# 13-Power-P3V3.net
KiCad netlist of a schematic drawn in Altium Designer
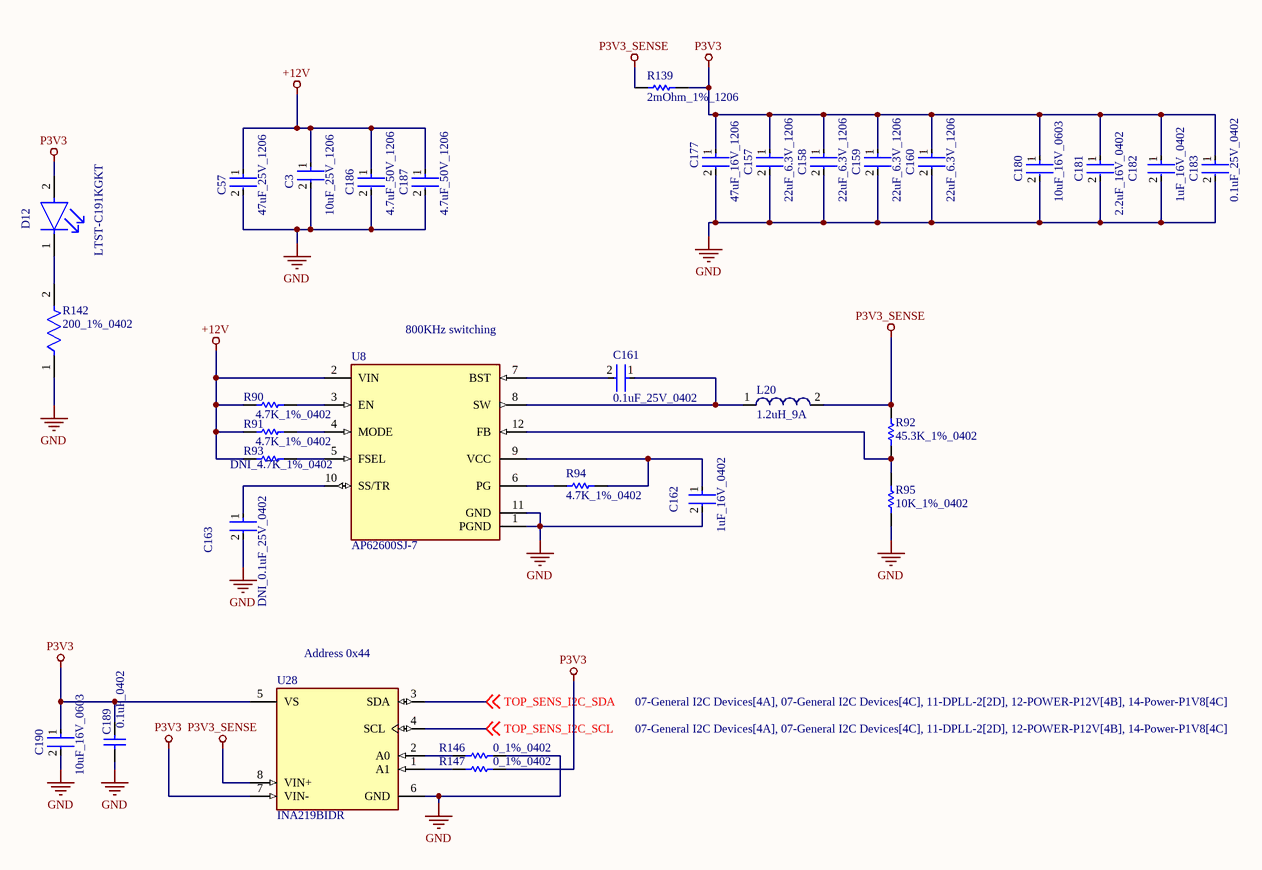
[diagram p0: 13-Power-P3V3.SchDoc]

(export (version "E")
  (design (tool "Eeschema 10.0.6"))
  (components
    (comp (ref "C3")
      (value "10uF_25V_1206")
      (footprint "FP-1206-L_3_2_0_2-W_1_6_0-IPC_A")
      (description "General Purpose Ceramic Capacitor, 1206, 10uF, 20%, X5R, 15%, 25V")
      (fields (field (name "TOLERANCE") "20%"))
      (libsource (lib "Altium Content Vault") (part "02cd4be3c70576c341d710602a673aa"))
    )
    (comp (ref "C57")
      (value "47uF_25V_1206")
      (footprint "FP-C3216-160-0_2-MFG")
      (description "Multilayer Ceramic Capacitors 47uF ±20% 25V X5R SMD 1206")
      (fields (field (name "VOLTAGE") "25V") (field (name "TOLERANCE") "20%"))
      (libsource (lib "Altium Content Vault") (part "11868f565c42a9108669ba33697ecf6"))
    )
    (comp (ref "C157")
      (value "22uF_6.3V_1206")
      (footprint "FP-1206-L_3_2_0_2-W_1_6_0-IPC_C")
      (description "General Purpose Ceramic Capacitor, 1206, 22uF, 20%, X5R, 15%, 6.3V")
      (fields (field (name "TOLERANCE") "20%") (field (name "VOLTAGE") "6.3V"))
      (libsource (lib "Altium Content Vault") (part "02cd4be3c70576c341d710602a673aa"))
    )
    (comp (ref "C158")
      (value "22uF_6.3V_1206")
      (footprint "FP-1206-L_3_2_0_2-W_1_6_0-IPC_C")
      (description "General Purpose Ceramic Capacitor, 1206, 22uF, 20%, X5R, 15%, 6.3V")
      (fields (field (name "TOLERANCE") "20%") (field (name "VOLTAGE") "6.3V"))
      (libsource (lib "Altium Content Vault") (part "02cd4be3c70576c341d710602a673aa"))
    )
    (comp (ref "C159")
      (value "22uF_6.3V_1206")
      (footprint "FP-1206-L_3_2_0_2-W_1_6_0-IPC_C")
      (description "General Purpose Ceramic Capacitor, 1206, 22uF, 20%, X5R, 15%, 6.3V")
      (fields (field (name "TOLERANCE") "20%") (field (name "VOLTAGE") "6.3V"))
      (libsource (lib "Altium Content Vault") (part "02cd4be3c70576c341d710602a673aa"))
    )
    (comp (ref "C160")
      (value "22uF_6.3V_1206")
      (footprint "FP-1206-L_3_2_0_2-W_1_6_0-IPC_C")
      (description "General Purpose Ceramic Capacitor, 1206, 22uF, 20%, X5R, 15%, 6.3V")
      (fields (field (name "TOLERANCE") "20%") (field (name "VOLTAGE") "6.3V"))
      (libsource (lib "Altium Content Vault") (part "02cd4be3c70576c341d710602a673aa"))
    )
    (comp (ref "C161")
      (value "0.1uF_25V_0402")
      (footprint "FP-0402-L_1_0_1-W_0_5_0_1-IPC_C")
      (description "General Purpose Ceramic Capacitor, 0402, 100nF, 10%, X7R, 15%, 25V")
      (fields (field (name "VOLTAGE") "25V") (field (name "TOLERANCE") "10%"))
      (libsource (lib "Altium Content Vault") (part "b4654b650e69147ec39a6b967a45e02"))
    )
    (comp (ref "C162")
      (value "1uF_16V_0402")
      (footprint "FP-0402-L_1_0_0_05-W_0_5-IPC_A")
      (description "None")
      (fields (field (name "TOLERANCE") "10%"))
      (libsource (lib "Altium Content Vault") (part "b4654b650e69147ec39a6b967a45e02"))
    )
    (comp (ref "C163")
      (value "DNI_0.1uF_25V_0402")
      (footprint "FP-0402-L_1_0_1-W_0_5_0_1-IPC_C")
      (description "General Purpose Ceramic Capacitor, 0402, 100nF, 10%, X7R, 15%, 25V")
      (fields (field (name "VOLTAGE") "25V") (field (name "TOLERANCE") "10%"))
      (libsource (lib "Altium Content Vault") (part "b4654b650e69147ec39a6b967a45e02"))
    )
    (comp (ref "C177")
      (value "47uF_16V_1206")
      (footprint "FP-C3216-160-0_2-MFG")
      (description "Multilayer Ceramic Capacitors 47uF ±20% 16V X5R SMD 1206")
      (fields (field (name "TOLERANCE") "20%"))
      (libsource (lib "Altium Content Vault") (part "11868f565c42a9108669ba33697ecf6"))
    )
    (comp (ref "C180")
      (value "10uF_16V_0603")
      (footprint "FP-0603-L_1_6_0_2-W_0_8_0-MFG")
      (description "Multilayer Ceramic Capacitor 10uF 16V X5R 20% SMD 0603 T/R")
      (fields (field (name "TOLERANCE") "20%"))
      (libsource (lib "Altium Content Vault") (part "b4654b650e69147ec39a6b967a45e02"))
    )
    (comp (ref "C181")
      (value "2.2uF_16V_0402")
      (footprint "FP-C1005-050-0_05-IPC_A")
      (description "Multilayer Ceramic Capacitors 2.2μF ±10% 16V X5R SMD 0402")
      (fields (field (name "TOLERANCE") "10%"))
      (libsource (lib "Altium Content Vault") (part "b4654b650e69147ec39a6b967a45e02"))
    )
    (comp (ref "C182")
      (value "1uF_16V_0402")
      (footprint "FP-0402-L_1_0_0_05-W_0_5-IPC_A")
      (description "None")
      (fields (field (name "TOLERANCE") "10%"))
      (libsource (lib "Altium Content Vault") (part "b4654b650e69147ec39a6b967a45e02"))
    )
    (comp (ref "C183")
      (value "0.1uF_25V_0402")
      (footprint "FP-0402-L_1_0_1-W_0_5_0_1-IPC_C")
      (description "General Purpose Ceramic Capacitor, 0402, 100nF, 10%, X7R, 15%, 25V")
      (fields (field (name "VOLTAGE") "25V") (field (name "TOLERANCE") "10%"))
      (libsource (lib "Altium Content Vault") (part "b4654b650e69147ec39a6b967a45e02"))
    )
    (comp (ref "C186")
      (value "4.7uF_50V_1206")
      (footprint "FP-GRM31C-0_2-e0_3_0_8-IPC_C")
      (description "Chip Multilayer Ceramic Capacitors for General Purpose, 1206, 4.7uF, X7R, 15%, 10%, 50V")
      (fields (field (name "VOLTAGE") "50V") (field (name "TOLERANCE") "10%"))
      (libsource (lib "Altium Content Vault") (part "02cd4be3c70576c341d710602a673aa"))
    )
    (comp (ref "C187")
      (value "4.7uF_50V_1206")
      (footprint "FP-GRM31C-0_2-e0_3_0_8-IPC_C")
      (description "Chip Multilayer Ceramic Capacitors for General Purpose, 1206, 4.7uF, X7R, 15%, 10%, 50V")
      (fields (field (name "VOLTAGE") "50V") (field (name "TOLERANCE") "10%"))
      (libsource (lib "Altium Content Vault") (part "02cd4be3c70576c341d710602a673aa"))
    )
    (comp (ref "C189")
      (value "0.1uF_0402")
      (footprint "CAPC1005X56X25NL10T15")
      (fields
        (field (name "PART NUMBER") "LD02YD104KAB2A")
        (field (name "MANUFACTURER") "AVX Interconnect / Elco")
      )
      (libsource (lib "Altium Content Vault") (part "CAP"))
    )
    (comp (ref "C190")
      (value "10uF_16V_0603")
      (footprint "FP-0603-L_1_6_0_2-W_0_8_0-MFG")
      (description "Multilayer Ceramic Capacitor 10uF 16V X5R 20% SMD 0603 T/R")
      (fields (field (name "TOLERANCE") "20%"))
      (libsource (lib "Altium Content Vault") (part "b4654b650e69147ec39a6b967a45e02"))
    )
    (comp (ref "D12")
      (value "LTST-C191KGKT")
      (footprint "FP-LTST-C191KGKT-MFG")
      (description "LED GREEN CLEAR SMD")
      (libsource (lib "Altium Content Vault") (part "8706943c75ba83719d021d2fdc84c58"))
    )
    (comp (ref "L20")
      (value "1.2uH_9A")
      (footprint "WE-LHMI 7050")
      (description "SMD Power Inductor WE-LHMI, L=1.2 µH")
      (fields (field (name "MANUFACTURER") "Wuerth Elektronik") (field (name "PARTNUMBER") "74437349012"))
      (libsource (lib "Altium Content Vault") (part "WE-IND-INDUCTOR-2"))
    )
    (comp (ref "R90")
      (value "4.7K_1%_0402")
      (footprint "RESC1005X40X25NL10T10")
      (fields (field (name "MANUFACTURER") "Bourns") (field (name "PART NUMBER") "CR0402-FX-4701GLF"))
      (libsource (lib "Altium Content Vault") (part "RES"))
    )
    (comp (ref "R91")
      (value "4.7K_1%_0402")
      (footprint "RESC1005X40X25NL10T10")
      (fields (field (name "MANUFACTURER") "Bourns") (field (name "PART NUMBER") "CR0402-FX-4701GLF"))
      (libsource (lib "Altium Content Vault") (part "RES"))
    )
    (comp (ref "R92")
      (value "45.3K_1%_0402")
      (footprint "RESC1005X40X25ML05T10")
      (fields (field (name "PART NUMBER") "RC0402FR-0745K3L") (field (name "MANUFACTURER") "Yageo / Phycomp"))
      (libsource (lib "Altium Content Vault") (part "RES"))
    )
    (comp (ref "R93")
      (value "DNI_4.7K_1%_0402")
      (footprint "RESC1005X40X25NL10T10")
      (fields (field (name "MANUFACTURER") "Bourns") (field (name "PART NUMBER") "CR0402-FX-4701GLF"))
      (libsource (lib "Altium Content Vault") (part "RES"))
    )
    (comp (ref "R94")
      (value "4.7K_1%_0402")
      (footprint "RESC1005X40X25NL10T10")
      (fields (field (name "MANUFACTURER") "Bourns") (field (name "PART NUMBER") "CR0402-FX-4701GLF"))
      (libsource (lib "Altium Content Vault") (part "RES"))
    )
    (comp (ref "R95")
      (value "10K_1%_0402")
      (footprint "RESC1005X40X25NL10T10")
      (fields (field (name "MANUFACTURER") "Bourns") (field (name "PART NUMBER") "CR0402-FX-1002GLF"))
      (libsource (lib "Altium Content Vault") (part "RES"))
    )
    (comp (ref "R139")
      (value "2mOhm_1%_1206")
      (footprint "RESC3216X89X64NL25T25")
      (fields (field (name "MANUFACTURER") "Vishay Dale") (field (name "PART NUMBER") "WSL12062L000FEA18"))
      (libsource (lib "Altium Content Vault") (part "RES"))
    )
    (comp (ref "R142")
      (value "200_1%_0402")
      (footprint "FP-ERJ2RK-IPC_A")
      (description "RES SMD 200 OHM 1% 1/10W 0402")
      (fields (field (name "TOLERANCE") "1%"))
      (libsource (lib "Altium Content Vault") (part "1029c3af85768c4190bb7ad29bc67b5"))
    )
    (comp (ref "R146")
      (value "0_1%_0402")
      (footprint "RESC1005X40X25LL05T05")
      (description "Chip Resistor, 0 Ohm, 0.1 W, -55 to 155 degC, 0402 (1005 Metric), RoHS, Tape and Reel")
      (fields (field (name "MANUFACTURER") "Panasonic") (field (name "TOLERANCE") "5%"))
      (libsource (lib "Altium Content Vault") (part "RES-2"))
    )
    (comp (ref "R147")
      (value "0_1%_0402")
      (footprint "RESC1005X40X25LL05T05")
      (description "Chip Resistor, 0 Ohm, 0.1 W, -55 to 155 degC, 0402 (1005 Metric), RoHS, Tape and Reel")
      (fields (field (name "MANUFACTURER") "Panasonic") (field (name "TOLERANCE") "5%"))
      (libsource (lib "Altium Content Vault") (part "RES-2"))
    )
    (comp (ref "U8")
      (value "AP62600SJ-7")
      (footprint "FP-V-QFN2030-12_Type_A-MFG")
      (description "DCDC CONV HV BUCK,V-QFN2030-12")
      (libsource (lib "Altium Content Vault") (part "03c86ce2703f4b33b3045e94f7be521"))
    )
    (comp (ref "U28")
      (value "INA219BIDR")
      (footprint "FP-D0008A-MFG")
      (description "IC MONITOR PWR/CURR BIDIR 8-SOIC")
      (libsource (lib "Altium Content Vault") (part "41cc1aee4cbc9fa2660a15773fa0e79"))
    )
  )
  (nets
    (net (code "1") (name "+12V") (class "Default")
      (node (ref "C186") (pin "1") (pinfunction "1_1") (pintype "passive"))
      (node (ref "C187") (pin "1") (pinfunction "1_1") (pintype "passive"))
      (node (ref "C3") (pin "1") (pinfunction "1_1") (pintype "passive"))
      (node (ref "C57") (pin "1") (pinfunction "1_1") (pintype "passive"))
      (node (ref "R90") (pin "1") (pinfunction "1_1") (pintype "passive"))
      (node (ref "R91") (pin "1") (pinfunction "1_1") (pintype "passive"))
      (node (ref "R93") (pin "1") (pinfunction "1_1") (pintype "passive"))
      (node (ref "U8") (pin "2") (pinfunction "VIN_2") (pintype "power_in"))
    )
    (net (code "2") (name "GND") (class "Default")
      (node (ref "C157") (pin "2") (pinfunction "2_2") (pintype "passive"))
      (node (ref "C158") (pin "2") (pinfunction "2_2") (pintype "passive"))
      (node (ref "C159") (pin "2") (pinfunction "2_2") (pintype "passive"))
      (node (ref "C160") (pin "2") (pinfunction "2_2") (pintype "passive"))
      (node (ref "C162") (pin "2") (pinfunction "2_2") (pintype "passive"))
      (node (ref "C163") (pin "2") (pinfunction "2_2") (pintype "passive"))
      (node (ref "C177") (pin "2") (pinfunction "2_2") (pintype "passive"))
      (node (ref "C180") (pin "2") (pinfunction "2_2") (pintype "passive"))
      (node (ref "C181") (pin "2") (pinfunction "2_2") (pintype "passive"))
      (node (ref "C182") (pin "2") (pinfunction "2_2") (pintype "passive"))
      (node (ref "C183") (pin "2") (pinfunction "2_2") (pintype "passive"))
      (node (ref "C186") (pin "2") (pinfunction "2_2") (pintype "passive"))
      (node (ref "C187") (pin "2") (pinfunction "2_2") (pintype "passive"))
      (node (ref "C189") (pin "1") (pinfunction "1_1") (pintype "passive"))
      (node (ref "C190") (pin "2") (pinfunction "2_2") (pintype "passive"))
      (node (ref "C3") (pin "2") (pinfunction "2_2") (pintype "passive"))
      (node (ref "C57") (pin "2") (pinfunction "2_2") (pintype "passive"))
      (node (ref "R142") (pin "1") (pinfunction "1_1") (pintype "passive"))
      (node (ref "R146") (pin "2") (pinfunction "2_2") (pintype "passive"))
      (node (ref "R95") (pin "1") (pinfunction "1_1") (pintype "passive"))
      (node (ref "U28") (pin "6") (pinfunction "GND_6") (pintype "power_in"))
      (node (ref "U8") (pin "1") (pinfunction "PGND_1") (pintype "power_in"))
      (node (ref "U8") (pin "11") (pinfunction "GND_11") (pintype "power_in"))
    )
    (net (code "3") (name "Net-(D12-C)") (class "Default")
      (node (ref "D12") (pin "1") (pinfunction "C_1") (pintype "passive"))
      (node (ref "R142") (pin "2") (pinfunction "2_2") (pintype "passive"))
    )
    (net (code "4") (name "Net-(U8-BST)") (class "Default")
      (node (ref "C161") (pin "2") (pinfunction "2_2") (pintype "passive"))
      (node (ref "U8") (pin "7") (pinfunction "BST_7") (pintype "input"))
    )
    (net (code "5") (name "Net-(U8-EN)") (class "Default")
      (node (ref "R90") (pin "2") (pinfunction "2_2") (pintype "passive"))
      (node (ref "U8") (pin "3") (pinfunction "EN_3") (pintype "input"))
    )
    (net (code "6") (name "Net-(U8-FB)") (class "Default")
      (node (ref "R92") (pin "1") (pinfunction "1_1") (pintype "passive"))
      (node (ref "R95") (pin "2") (pinfunction "2_2") (pintype "passive"))
      (node (ref "U8") (pin "12") (pinfunction "FB_12") (pintype "input"))
    )
    (net (code "7") (name "Net-(U8-FSEL)") (class "Default")
      (node (ref "R93") (pin "2") (pinfunction "2_2") (pintype "passive"))
      (node (ref "U8") (pin "5") (pinfunction "FSEL_5") (pintype "input"))
    )
    (net (code "8") (name "Net-(U8-MODE)") (class "Default")
      (node (ref "R91") (pin "2") (pinfunction "2_2") (pintype "passive"))
      (node (ref "U8") (pin "4") (pinfunction "MODE_4") (pintype "input"))
    )
    (net (code "9") (name "Net-(U8-PG)") (class "Default")
      (node (ref "R94") (pin "2") (pinfunction "2_2") (pintype "passive"))
      (node (ref "U8") (pin "6") (pinfunction "PG_6") (pintype "open_collector"))
    )
    (net (code "10") (name "Net-(U8-SS{slash}TR)") (class "Default")
      (node (ref "C163") (pin "1") (pinfunction "1_1") (pintype "passive"))
      (node (ref "U8") (pin "10") (pinfunction "SS/TR_10") (pintype "bidirectional"))
    )
    (net (code "11") (name "Net-(U8-SW)") (class "Default")
      (node (ref "C161") (pin "1") (pinfunction "1_1") (pintype "passive"))
      (node (ref "L20") (pin "1") (pinfunction "1_1") (pintype "passive"))
      (node (ref "U8") (pin "8") (pinfunction "SW_8") (pintype "output"))
    )
    (net (code "12") (name "Net-(U8-VCC)") (class "Default")
      (node (ref "C162") (pin "1") (pinfunction "1_1") (pintype "passive"))
      (node (ref "R94") (pin "1") (pinfunction "1_1") (pintype "passive"))
      (node (ref "U8") (pin "9") (pinfunction "VCC_9") (pintype "power_in"))
    )
    (net (code "13") (name "Net-(U28-A0)") (class "Default")
      (node (ref "R146") (pin "1") (pinfunction "1_1") (pintype "passive"))
      (node (ref "U28") (pin "2") (pinfunction "A0_2") (pintype "input"))
    )
    (net (code "14") (name "Net-(U28-A1)") (class "Default")
      (node (ref "R147") (pin "1") (pinfunction "1_1") (pintype "passive"))
      (node (ref "U28") (pin "1") (pinfunction "A1_1") (pintype "input"))
    )
    (net (code "15") (name "P3V3") (class "Default")
      (node (ref "C157") (pin "1") (pinfunction "1_1") (pintype "passive"))
      (node (ref "C158") (pin "1") (pinfunction "1_1") (pintype "passive"))
      (node (ref "C159") (pin "1") (pinfunction "1_1") (pintype "passive"))
      (node (ref "C160") (pin "1") (pinfunction "1_1") (pintype "passive"))
      (node (ref "C177") (pin "1") (pinfunction "1_1") (pintype "passive"))
      (node (ref "C180") (pin "1") (pinfunction "1_1") (pintype "passive"))
      (node (ref "C181") (pin "1") (pinfunction "1_1") (pintype "passive"))
      (node (ref "C182") (pin "1") (pinfunction "1_1") (pintype "passive"))
      (node (ref "C183") (pin "1") (pinfunction "1_1") (pintype "passive"))
      (node (ref "C189") (pin "2") (pinfunction "2_2") (pintype "passive"))
      (node (ref "C190") (pin "1") (pinfunction "1_1") (pintype "passive"))
      (node (ref "D12") (pin "2") (pinfunction "A_2") (pintype "passive"))
      (node (ref "R139") (pin "2") (pinfunction "2_2") (pintype "passive"))
      (node (ref "R147") (pin "2") (pinfunction "2_2") (pintype "passive"))
      (node (ref "U28") (pin "5") (pinfunction "VS_5") (pintype "power_in"))
      (node (ref "U28") (pin "7") (pinfunction "VIN-_7") (pintype "input"))
    )
    (net (code "16") (name "P3V3_SENSE") (class "Default")
      (node (ref "L20") (pin "2") (pinfunction "2_2") (pintype "passive"))
      (node (ref "R139") (pin "1") (pinfunction "1_1") (pintype "passive"))
      (node (ref "R92") (pin "2") (pinfunction "2_2") (pintype "passive"))
      (node (ref "U28") (pin "8") (pinfunction "VIN+_8") (pintype "input"))
    )
    (net (code "17") (name "TOP_SENS_I2C_SCL") (class "Default")
      (node (ref "U28") (pin "4") (pinfunction "SCL_4") (pintype "bidirectional"))
    )
    (net (code "18") (name "TOP_SENS_I2C_SDA") (class "Default")
      (node (ref "U28") (pin "3") (pinfunction "SDA_3") (pintype "bidirectional"))
    )
  )
)
